# Xbee_Trigger_Breakout.net
KiCad netlist of a schematic drawn in EAGLE
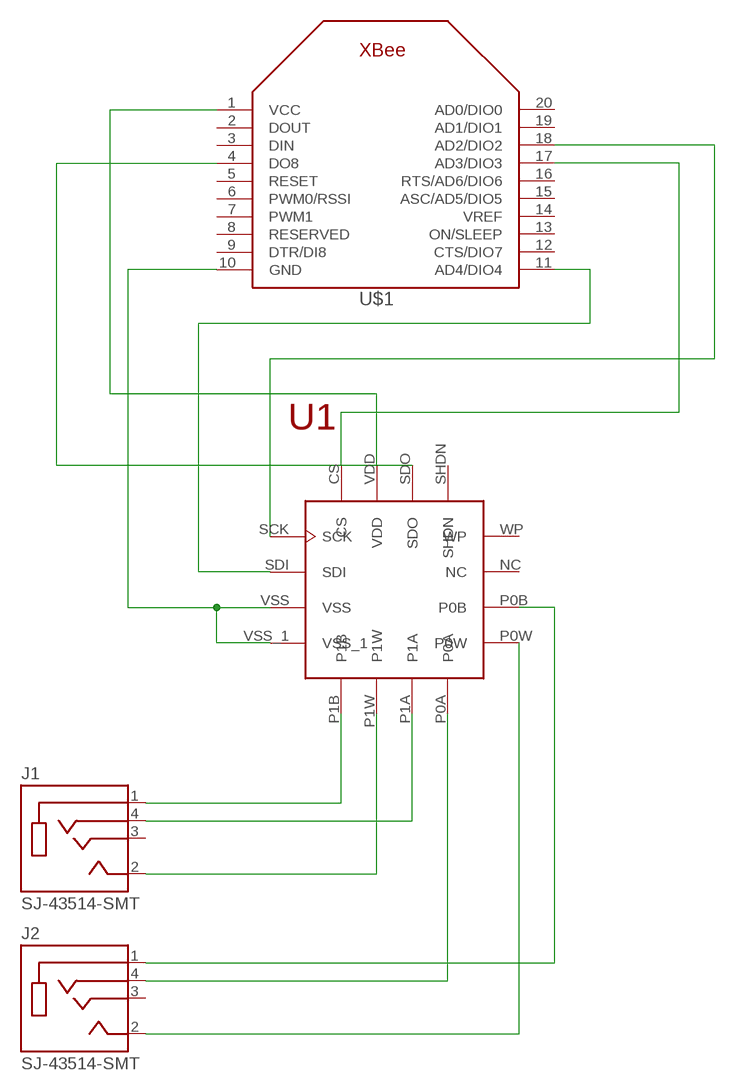
[diagram p0: schematic, sheet 1]

(export (version "E")
  (design (tool "Eeschema 10.0.6"))
  (components
    (comp (ref "J1")
      (value "SJ-43514-SMT")
      (footprint "eagle-import:CUI_SJ-43514-SMT")
      (fields (field (name "MF") "CUI"))
      (libsource (lib "eagle-import") (part "SJ-43514-SMT"))
    )
    (comp (ref "J2")
      (value "SJ-43514-SMT")
      (footprint "eagle-import:CUI_SJ-43514-SMT")
      (fields (field (name "MF") "CUI"))
      (libsource (lib "eagle-import") (part "SJ-43514-SMT"))
    )
    (comp (ref "U$1")
      (value "XBEE")
      (footprint "eagle-import:XBEE")
      (libsource (lib "eagle-import") (part "XBEE"))
    )
    (comp (ref "U1")
      (value "MCP4261")
      (footprint "eagle-import:2CH_DIGITAL_POT_QFN")
      (libsource (lib "eagle-import") (part "MCP4261"))
    )
  )
  (nets
    (net (code "1") (name "Net-(J1-RING2)") (class "Default")
      (node (ref "J1") (pin "4") (pinfunction "RING2_4") (pintype "passive"))
      (node (ref "U1") (pin "P1A") (pinfunction "P1A_P1A") (pintype "bidirectional"))
    )
    (net (code "2") (name "Net-(J1-SLEEVE)") (class "Default")
      (node (ref "J1") (pin "1") (pinfunction "SLEEVE_1") (pintype "passive"))
      (node (ref "U1") (pin "P1B") (pinfunction "P1B_P1B") (pintype "bidirectional"))
    )
    (net (code "3") (name "Net-(J1-TIP)") (class "Default")
      (node (ref "J1") (pin "2") (pinfunction "TIP_2") (pintype "passive"))
      (node (ref "U1") (pin "P1W") (pinfunction "P1W_P1W") (pintype "output"))
    )
    (net (code "4") (name "Net-(J2-RING2)") (class "Default")
      (node (ref "J2") (pin "4") (pinfunction "RING2_4") (pintype "passive"))
      (node (ref "U1") (pin "P0A") (pinfunction "P0A_P0A") (pintype "bidirectional"))
    )
    (net (code "5") (name "Net-(J2-SLEEVE)") (class "Default")
      (node (ref "J2") (pin "1") (pinfunction "SLEEVE_1") (pintype "passive"))
      (node (ref "U1") (pin "P0B") (pinfunction "P0B_P0B") (pintype "bidirectional"))
    )
    (net (code "6") (name "Net-(J2-TIP)") (class "Default")
      (node (ref "J2") (pin "2") (pinfunction "TIP_2") (pintype "passive"))
      (node (ref "U1") (pin "P0W") (pinfunction "P0W_P0W") (pintype "output"))
    )
    (net (code "7") (name "Net-(U$1-AD2{slash}DIO2)") (class "Default")
      (node (ref "U$1") (pin "18") (pinfunction "AD2/DIO2_18") (pintype "bidirectional"))
      (node (ref "U1") (pin "SCK") (pinfunction "SCK_SCK") (pintype "input"))
    )
    (net (code "8") (name "Net-(U$1-AD3{slash}DIO3)") (class "Default")
      (node (ref "U$1") (pin "17") (pinfunction "AD3/DIO3_17") (pintype "bidirectional"))
      (node (ref "U1") (pin "CS") (pinfunction "CS_CS") (pintype "bidirectional"))
    )
    (net (code "9") (name "Net-(U$1-AD4{slash}DIO4)") (class "Default")
      (node (ref "U$1") (pin "11") (pinfunction "AD4/DIO4_11") (pintype "bidirectional"))
      (node (ref "U1") (pin "SDI") (pinfunction "SDI_SDI") (pintype "input"))
    )
    (net (code "10") (name "Net-(U$1-DO8)") (class "Default")
      (node (ref "U$1") (pin "4") (pinfunction "DO8_4") (pintype "output"))
      (node (ref "U1") (pin "SDO") (pinfunction "SDO_SDO") (pintype "output"))
    )
    (net (code "11") (name "Net-(U$1-GND)") (class "Default")
      (node (ref "U$1") (pin "10") (pinfunction "GND_10") (pintype "power_in"))
      (node (ref "U1") (pin "VSS") (pinfunction "VSS_VSS") (pintype "power_in"))
      (node (ref "U1") (pin "VSS_1") (pinfunction "VSS_1_VSS_1") (pintype "power_in"))
    )
    (net (code "12") (name "Net-(U$1-VCC)") (class "Default")
      (node (ref "U$1") (pin "1") (pinfunction "VCC_1") (pintype "power_in"))
      (node (ref "U1") (pin "VDD") (pinfunction "VDD_VDD") (pintype "power_in"))
    )
    (net (code "13") (name "unconnected-(J1-RING1-Pad3)") (class "Default")
      (node (ref "J1") (pin "3") (pinfunction "RING1_3") (pintype "passive"))
    )
    (net (code "14") (name "unconnected-(J2-RING1-Pad3)") (class "Default")
      (node (ref "J2") (pin "3") (pinfunction "RING1_3") (pintype "passive"))
    )
    (net (code "15") (name "unconnected-(U$1-AD0{slash}DIO0-Pad20)") (class "Default")
      (node (ref "U$1") (pin "20") (pinfunction "AD0/DIO0_20") (pintype "bidirectional"))
    )
    (net (code "16") (name "unconnected-(U$1-AD1{slash}DIO1-Pad19)") (class "Default")
      (node (ref "U$1") (pin "19") (pinfunction "AD1/DIO1_19") (pintype "bidirectional"))
    )
    (net (code "17") (name "unconnected-(U$1-ASC{slash}AD5{slash}DIO5-Pad15)") (class "Default")
      (node (ref "U$1") (pin "15") (pinfunction "ASC/AD5/DIO5_15") (pintype "bidirectional"))
    )
    (net (code "18") (name "unconnected-(U$1-CTS{slash}DIO7-Pad12)") (class "Default")
      (node (ref "U$1") (pin "12") (pinfunction "CTS/DIO7_12") (pintype "bidirectional"))
    )
    (net (code "19") (name "unconnected-(U$1-DIN-Pad3)") (class "Default")
      (node (ref "U$1") (pin "3") (pinfunction "DIN_3") (pintype "input"))
    )
    (net (code "20") (name "unconnected-(U$1-DOUT-Pad2)") (class "Default")
      (node (ref "U$1") (pin "2") (pinfunction "DOUT_2") (pintype "output"))
    )
    (net (code "21") (name "unconnected-(U$1-DTR{slash}DI8-Pad9)") (class "Default")
      (node (ref "U$1") (pin "9") (pinfunction "DTR/DI8_9") (pintype "input"))
    )
    (net (code "22") (name "unconnected-(U$1-ON{slash}SLEEP-Pad13)") (class "Default")
      (node (ref "U$1") (pin "13") (pinfunction "ON/SLEEP_13") (pintype "output"))
    )
    (net (code "23") (name "unconnected-(U$1-PWM0{slash}RSSI-Pad6)") (class "Default")
      (node (ref "U$1") (pin "6") (pinfunction "PWM0/RSSI_6") (pintype "output"))
    )
    (net (code "24") (name "unconnected-(U$1-PWM1-Pad7)") (class "Default")
      (node (ref "U$1") (pin "7") (pinfunction "PWM1_7") (pintype "output"))
    )
    (net (code "25") (name "unconnected-(U$1-RESERVED-Pad8)") (class "Default")
      (node (ref "U$1") (pin "8") (pinfunction "RESERVED_8") (pintype "no_connect"))
    )
    (net (code "26") (name "unconnected-(U$1-RESET-Pad5)") (class "Default")
      (node (ref "U$1") (pin "5") (pinfunction "RESET_5") (pintype "input"))
    )
    (net (code "27") (name "unconnected-(U$1-RTS{slash}AD6{slash}DIO6-Pad16)") (class "Default")
      (node (ref "U$1") (pin "16") (pinfunction "RTS/AD6/DIO6_16") (pintype "bidirectional"))
    )
    (net (code "28") (name "unconnected-(U$1-VREF-Pad14)") (class "Default")
      (node (ref "U$1") (pin "14") (pinfunction "VREF_14") (pintype "input"))
    )
    (net (code "29") (name "unconnected-(U1-PadNC)") (class "Default")
      (node (ref "U1") (pin "NC") (pinfunction "NC_NC") (pintype "no_connect"))
    )
    (net (code "30") (name "unconnected-(U1-PadSHDN)") (class "Default")
      (node (ref "U1") (pin "SHDN") (pinfunction "SHDN_SHDN") (pintype "input"))
    )
    (net (code "31") (name "unconnected-(U1-PadWP)") (class "Default")
      (node (ref "U1") (pin "WP") (pinfunction "WP_WP") (pintype "bidirectional"))
    )
  )
)
